# mowgli_1.net
KiCad netlist of a schematic drawn in EAGLE
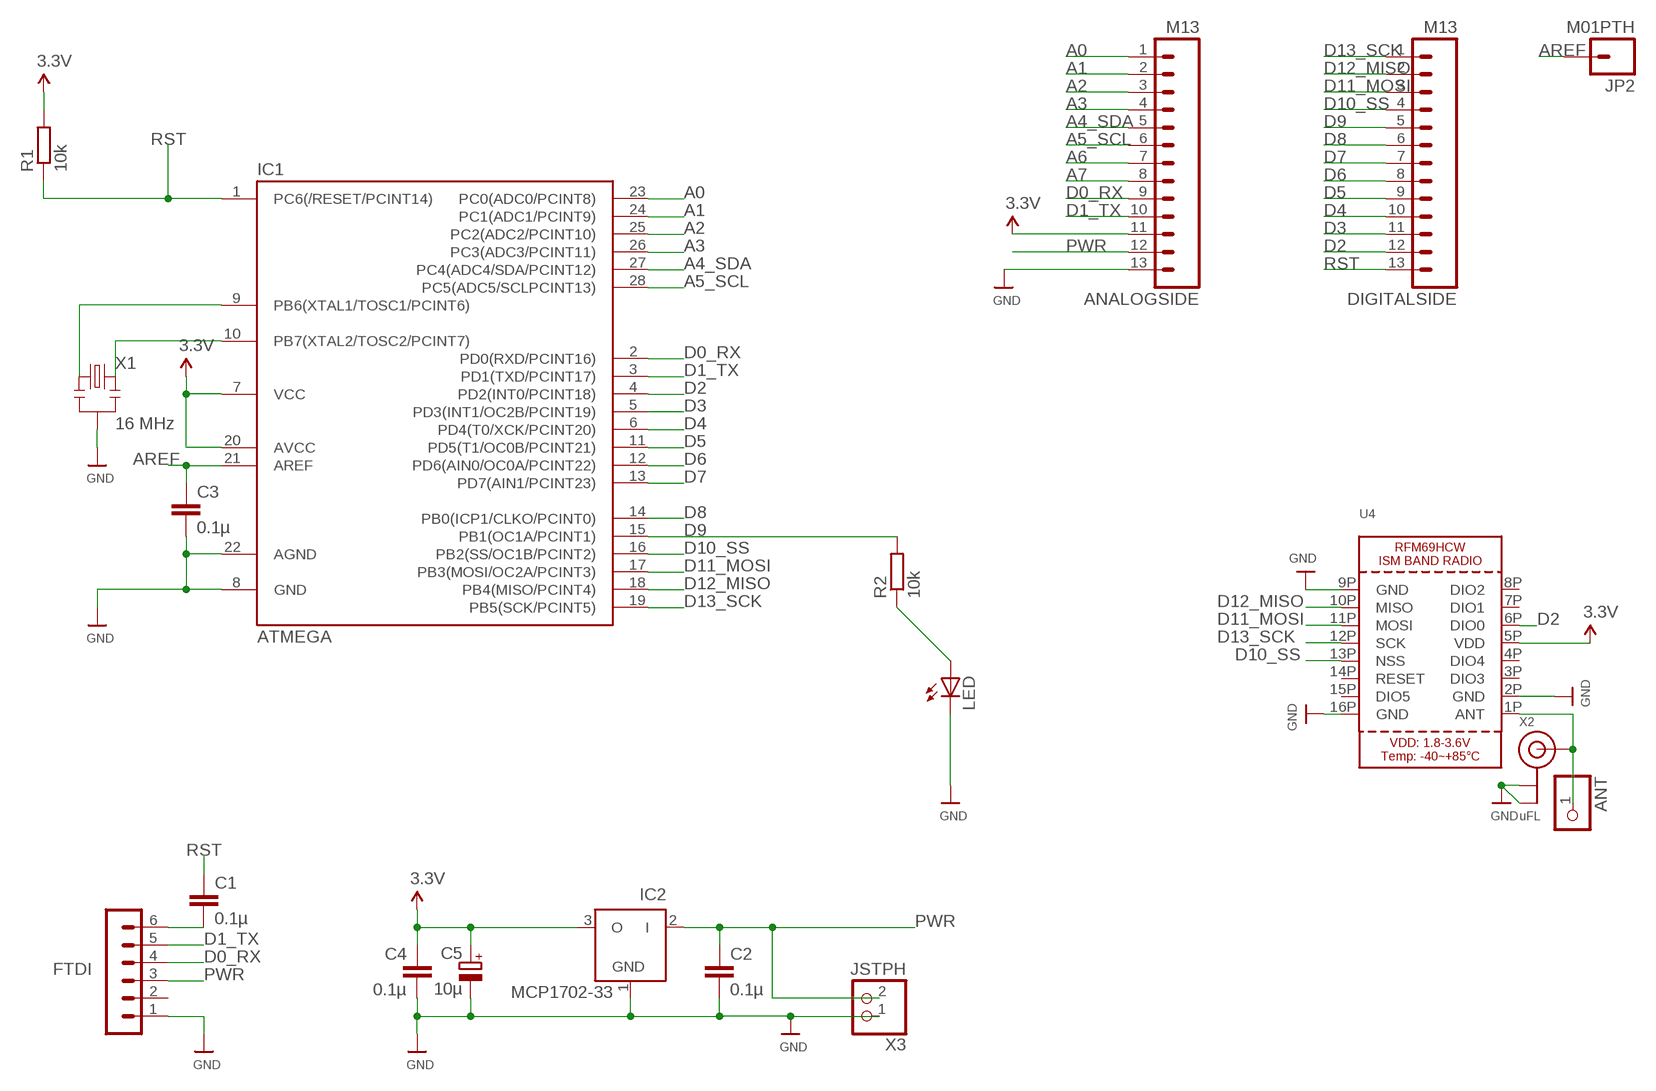
[diagram p0: schematic, sheet 1]

(export (version "E")
  (design (tool "Eeschema 10.0.6"))
  (components
    (comp (ref "ANALOGSIDE")
      (value "M13")
      (footprint "eagle-import:1X13")
      (libsource (lib "eagle-import") (part "M13"))
    )
    (comp (ref "ANT")
      (value "HEADER-1X1ROUND")
      (footprint "eagle-import:1X01_ROUND")
      (libsource (lib "eagle-import") (part "HEADER-1X1ROUND"))
    )
    (comp (ref "C1")
      (value "0.1µ")
      (footprint "eagle-import:C025-024X044")
      (libsource (lib "eagle-import") (part "C-EU025-024X044"))
    )
    (comp (ref "C2")
      (value "0.1µ")
      (footprint "eagle-import:C025-024X044")
      (libsource (lib "eagle-import") (part "C-EU025-024X044"))
    )
    (comp (ref "C3")
      (value "0.1µ")
      (footprint "eagle-import:C025-024X044")
      (libsource (lib "eagle-import") (part "C-EU025-024X044"))
    )
    (comp (ref "C4")
      (value "0.1µ")
      (footprint "eagle-import:C025-024X044")
      (libsource (lib "eagle-import") (part "C-EU025-024X044"))
    )
    (comp (ref "C5")
      (value "10µ")
      (footprint "eagle-import:E1,8-4")
      (libsource (lib "eagle-import") (part "CPOL-EUE1.8-4"))
    )
    (comp (ref "DIGITALSIDE")
      (value "M13")
      (footprint "eagle-import:1X13")
      (libsource (lib "eagle-import") (part "M13"))
    )
    (comp (ref "FTDI")
      (value "FTDI")
      (footprint "eagle-import:MA06-1")
      (libsource (lib "eagle-import") (part "MA06-1"))
    )
    (comp (ref "IC1")
      (value "ATMEGA")
      (footprint "eagle-import:DIL28-3")
      (libsource (lib "eagle-import") (part "ATMEGA48/88/168-PU"))
    )
    (comp (ref "IC2")
      (value "MCP1702-33")
      (footprint "eagle-import:TO92")
      (libsource (lib "eagle-import") (part "MCP1702Z"))
    )
    (comp (ref "JP2")
      (value "M01PTH")
      (footprint "eagle-import:1X01")
      (libsource (lib "eagle-import") (part "M01PTH"))
    )
    (comp (ref "LED")
      (value "LED3MM")
      (footprint "eagle-import:LED3MM")
      (libsource (lib "eagle-import") (part "LED3MM"))
    )
    (comp (ref "R1")
      (value "10k")
      (footprint "eagle-import:0204_7")
      (libsource (lib "eagle-import") (part "R-EU_0204/7"))
    )
    (comp (ref "R2")
      (value "10k")
      (footprint "eagle-import:0204_7")
      (libsource (lib "eagle-import") (part "R-EU_0204/7"))
    )
    (comp (ref "U4")
      (value "RFM69HCW_SMT")
      (footprint "eagle-import:RFMHCW_SMT")
      (libsource (lib "eagle-import") (part "RFM69HCW_SMT"))
    )
    (comp (ref "X1")
      (value "16 MHz")
      (footprint "eagle-import:RESONATOR-PTH")
      (libsource (lib "eagle-import") (part "RESONATORPTH"))
    )
    (comp (ref "X2")
      (value "uFL")
      (footprint "eagle-import:U.FL")
      (libsource (lib "eagle-import") (part "ANTENNA_U.FL"))
    )
    (comp (ref "X3")
      (value "JSTPH")
      (footprint "eagle-import:JSTPH2")
      (libsource (lib "eagle-import") (part "CON_JST_PH_2PIN"))
    )
  )
  (nets
    (net (code "1") (name "/A0") (class "Default")
      (node (ref "ANALOGSIDE") (pin "1") (pinfunction "1_1") (pintype "passive"))
      (node (ref "IC1") (pin "23") (pinfunction "PC0(ADC0/PCINT8)_23") (pintype "bidirectional"))
    )
    (net (code "2") (name "/A1") (class "Default")
      (node (ref "ANALOGSIDE") (pin "2") (pinfunction "2_2") (pintype "passive"))
      (node (ref "IC1") (pin "24") (pinfunction "PC1(ADC1/PCINT9)_24") (pintype "bidirectional"))
    )
    (net (code "3") (name "/A2") (class "Default")
      (node (ref "ANALOGSIDE") (pin "3") (pinfunction "3_3") (pintype "passive"))
      (node (ref "IC1") (pin "25") (pinfunction "PC2(ADC2/PCINT10)_25") (pintype "bidirectional"))
    )
    (net (code "4") (name "/A3") (class "Default")
      (node (ref "ANALOGSIDE") (pin "4") (pinfunction "4_4") (pintype "passive"))
      (node (ref "IC1") (pin "26") (pinfunction "PC3(ADC3/PCINT11)_26") (pintype "bidirectional"))
    )
    (net (code "5") (name "/A4_SDA") (class "Default")
      (node (ref "ANALOGSIDE") (pin "5") (pinfunction "5_5") (pintype "passive"))
      (node (ref "IC1") (pin "27") (pinfunction "PC4(ADC4/SDA/PCINT12)_27") (pintype "bidirectional"))
    )
    (net (code "6") (name "/A5_SCL") (class "Default")
      (node (ref "ANALOGSIDE") (pin "6") (pinfunction "6_6") (pintype "passive"))
      (node (ref "IC1") (pin "28") (pinfunction "PC5(ADC5/SCLPCINT13)_28") (pintype "bidirectional"))
    )
    (net (code "7") (name "/A6") (class "Default")
      (node (ref "ANALOGSIDE") (pin "7") (pinfunction "7_7") (pintype "passive"))
    )
    (net (code "8") (name "/A7") (class "Default")
      (node (ref "ANALOGSIDE") (pin "8") (pinfunction "8_8") (pintype "passive"))
    )
    (net (code "9") (name "/AREF") (class "Default")
      (node (ref "C3") (pin "1") (pinfunction "1_1") (pintype "passive"))
      (node (ref "IC1") (pin "21") (pinfunction "AREF_21") (pintype "passive"))
      (node (ref "JP2") (pin "1") (pinfunction "1_1") (pintype "passive"))
    )
    (net (code "10") (name "/D0_RX") (class "Default")
      (node (ref "ANALOGSIDE") (pin "9") (pinfunction "9_9") (pintype "passive"))
      (node (ref "FTDI") (pin "4") (pinfunction "4_4") (pintype "passive"))
      (node (ref "IC1") (pin "2") (pinfunction "PD0(RXD/PCINT16)_2") (pintype "bidirectional"))
    )
    (net (code "11") (name "/D1_TX") (class "Default")
      (node (ref "ANALOGSIDE") (pin "10") (pinfunction "10_10") (pintype "passive"))
      (node (ref "FTDI") (pin "5") (pinfunction "5_5") (pintype "passive"))
      (node (ref "IC1") (pin "3") (pinfunction "PD1(TXD/PCINT17)_3") (pintype "bidirectional"))
    )
    (net (code "12") (name "/D2") (class "Default")
      (node (ref "DIGITALSIDE") (pin "12") (pinfunction "12_12") (pintype "passive"))
      (node (ref "IC1") (pin "4") (pinfunction "PD2(INT0/PCINT18)_4") (pintype "bidirectional"))
      (node (ref "U4") (pin "6P") (pinfunction "DIO0_6P") (pintype "bidirectional"))
    )
    (net (code "13") (name "/D3") (class "Default")
      (node (ref "DIGITALSIDE") (pin "11") (pinfunction "11_11") (pintype "passive"))
      (node (ref "IC1") (pin "5") (pinfunction "PD3(INT1/OC2B/PCINT19)_5") (pintype "bidirectional"))
    )
    (net (code "14") (name "/D4") (class "Default")
      (node (ref "DIGITALSIDE") (pin "10") (pinfunction "10_10") (pintype "passive"))
      (node (ref "IC1") (pin "6") (pinfunction "PD4(T0/XCK/PCINT20)_6") (pintype "bidirectional"))
    )
    (net (code "15") (name "/D5") (class "Default")
      (node (ref "DIGITALSIDE") (pin "9") (pinfunction "9_9") (pintype "passive"))
      (node (ref "IC1") (pin "11") (pinfunction "PD5(T1/OC0B/PCINT21)_11") (pintype "bidirectional"))
    )
    (net (code "16") (name "/D6") (class "Default")
      (node (ref "DIGITALSIDE") (pin "8") (pinfunction "8_8") (pintype "passive"))
      (node (ref "IC1") (pin "12") (pinfunction "PD6(AIN0/OC0A/PCINT22)_12") (pintype "bidirectional"))
    )
    (net (code "17") (name "/D7") (class "Default")
      (node (ref "DIGITALSIDE") (pin "7") (pinfunction "7_7") (pintype "passive"))
      (node (ref "IC1") (pin "13") (pinfunction "PD7(AIN1/PCINT23)_13") (pintype "bidirectional"))
    )
    (net (code "18") (name "/D8") (class "Default")
      (node (ref "DIGITALSIDE") (pin "6") (pinfunction "6_6") (pintype "passive"))
      (node (ref "IC1") (pin "14") (pinfunction "PB0(ICP1/CLKO/PCINT0)_14") (pintype "bidirectional"))
    )
    (net (code "19") (name "/D9") (class "Default")
      (node (ref "DIGITALSIDE") (pin "5") (pinfunction "5_5") (pintype "passive"))
      (node (ref "IC1") (pin "15") (pinfunction "PB1(OC1A/PCINT1)_15") (pintype "bidirectional"))
      (node (ref "R2") (pin "2") (pinfunction "2_2") (pintype "passive"))
    )
    (net (code "20") (name "/D10_SS") (class "Default")
      (node (ref "DIGITALSIDE") (pin "4") (pinfunction "4_4") (pintype "passive"))
      (node (ref "IC1") (pin "16") (pinfunction "PB2(SS/OC1B/PCINT2)_16") (pintype "bidirectional"))
      (node (ref "U4") (pin "13P") (pinfunction "NSS_13P") (pintype "input"))
    )
    (net (code "21") (name "/D11_MOSI") (class "Default")
      (node (ref "DIGITALSIDE") (pin "3") (pinfunction "3_3") (pintype "passive"))
      (node (ref "IC1") (pin "17") (pinfunction "PB3(MOSI/OC2A/PCINT3)_17") (pintype "bidirectional"))
      (node (ref "U4") (pin "11P") (pinfunction "MOSI_11P") (pintype "input"))
    )
    (net (code "22") (name "/D12_MISO") (class "Default")
      (node (ref "DIGITALSIDE") (pin "2") (pinfunction "2_2") (pintype "passive"))
      (node (ref "IC1") (pin "18") (pinfunction "PB4(MISO/PCINT4)_18") (pintype "bidirectional"))
      (node (ref "U4") (pin "10P") (pinfunction "MISO_10P") (pintype "output"))
    )
    (net (code "23") (name "/D13_SCK") (class "Default")
      (node (ref "DIGITALSIDE") (pin "1") (pinfunction "1_1") (pintype "passive"))
      (node (ref "IC1") (pin "19") (pinfunction "PB5(SCK/PCINT5)_19") (pintype "bidirectional"))
      (node (ref "U4") (pin "12P") (pinfunction "SCK_12P") (pintype "input"))
    )
    (net (code "24") (name "/PWR") (class "Default")
      (node (ref "ANALOGSIDE") (pin "12") (pinfunction "12_12") (pintype "passive"))
      (node (ref "C2") (pin "1") (pinfunction "1_1") (pintype "passive"))
      (node (ref "FTDI") (pin "3") (pinfunction "3_3") (pintype "passive"))
      (node (ref "IC2") (pin "2") (pinfunction "I_2") (pintype "input"))
      (node (ref "X3") (pin "2") (pinfunction "2_2") (pintype "passive"))
    )
    (net (code "25") (name "/RST") (class "Default")
      (node (ref "C1") (pin "1") (pinfunction "1_1") (pintype "passive"))
      (node (ref "DIGITALSIDE") (pin "13") (pinfunction "13_13") (pintype "passive"))
      (node (ref "IC1") (pin "1") (pinfunction "PC6(/RESET/PCINT14)_1") (pintype "bidirectional"))
      (node (ref "R1") (pin "1") (pinfunction "1_1") (pintype "passive"))
    )
    (net (code "26") (name "3.3V") (class "Default")
      (node (ref "ANALOGSIDE") (pin "11") (pinfunction "11_11") (pintype "passive"))
      (node (ref "C4") (pin "1") (pinfunction "1_1") (pintype "passive"))
      (node (ref "C5") (pin "+") (pinfunction "+_+") (pintype "passive"))
      (node (ref "IC1") (pin "20") (pinfunction "AVCC_20") (pintype "passive"))
      (node (ref "IC1") (pin "7") (pinfunction "VCC_7") (pintype "power_in"))
      (node (ref "IC2") (pin "3") (pinfunction "O_3") (pintype "input"))
      (node (ref "R1") (pin "2") (pinfunction "2_2") (pintype "passive"))
      (node (ref "U4") (pin "5P") (pinfunction "VDD_5P") (pintype "power_in"))
    )
    (net (code "27") (name "GND") (class "Default")
      (node (ref "ANALOGSIDE") (pin "13") (pinfunction "13_13") (pintype "passive"))
      (node (ref "C2") (pin "2") (pinfunction "2_2") (pintype "passive"))
      (node (ref "C3") (pin "2") (pinfunction "2_2") (pintype "passive"))
      (node (ref "C4") (pin "2") (pinfunction "2_2") (pintype "passive"))
      (node (ref "C5") (pin "-") (pinfunction "-_-") (pintype "passive"))
      (node (ref "FTDI") (pin "1") (pinfunction "1_1") (pintype "passive"))
      (node (ref "IC1") (pin "22") (pinfunction "AGND_22") (pintype "power_in"))
      (node (ref "IC1") (pin "8") (pinfunction "GND_8") (pintype "power_in"))
      (node (ref "IC2") (pin "1") (pinfunction "GND_1") (pintype "power_in"))
      (node (ref "LED") (pin "K") (pinfunction "C_K") (pintype "passive"))
      (node (ref "U4") (pin "16P") (pinfunction "GND_16P") (pintype "power_in"))
      (node (ref "U4") (pin "2P") (pinfunction "GND_2P") (pintype "power_in"))
      (node (ref "U4") (pin "9P") (pinfunction "GND_9P") (pintype "power_in"))
      (node (ref "X1") (pin "2") (pinfunction "2_2") (pintype "passive"))
      (node (ref "X2") (pin "1") (pinfunction "GND_1") (pintype "passive"))
      (node (ref "X2") (pin "2") (pinfunction "GND_2") (pintype "passive"))
      (node (ref "X3") (pin "1") (pinfunction "1_1") (pintype "passive"))
    )
    (net (code "28") (name "Net-(C1-Pad2)") (class "Default")
      (node (ref "C1") (pin "2") (pinfunction "2_2") (pintype "passive"))
      (node (ref "FTDI") (pin "6") (pinfunction "6_6") (pintype "passive"))
    )
    (net (code "29") (name "Net-(IC1-PB6(XTAL1{slash}TOSC1{slash}PCINT6))") (class "Default")
      (node (ref "IC1") (pin "9") (pinfunction "PB6(XTAL1/TOSC1/PCINT6)_9") (pintype "bidirectional"))
      (node (ref "X1") (pin "1") (pinfunction "1_1") (pintype "passive"))
    )
    (net (code "30") (name "Net-(IC1-PB7(XTAL2{slash}TOSC2{slash}PCINT7))") (class "Default")
      (node (ref "IC1") (pin "10") (pinfunction "PB7(XTAL2/TOSC2/PCINT7)_10") (pintype "bidirectional"))
      (node (ref "X1") (pin "3") (pinfunction "3_3") (pintype "passive"))
    )
    (net (code "31") (name "Net-(LED-PadA)") (class "Default")
      (node (ref "LED") (pin "A") (pinfunction "A_A") (pintype "passive"))
      (node (ref "R2") (pin "1") (pinfunction "1_1") (pintype "passive"))
    )
    (net (code "32") (name "Net-(U4-ANT)") (class "Default")
      (node (ref "ANT") (pin "1") (pinfunction "1_1") (pintype "passive"))
      (node (ref "U4") (pin "1P") (pinfunction "ANT_1P") (pintype "bidirectional"))
      (node (ref "X2") (pin "3") (pinfunction "SIGNAL_3") (pintype "passive"))
    )
    (net (code "33") (name "unconnected-(FTDI-Pad2)") (class "Default")
      (node (ref "FTDI") (pin "2") (pinfunction "2_2") (pintype "passive"))
    )
    (net (code "34") (name "unconnected-(U4-DIO1-Pad7P)") (class "Default")
      (node (ref "U4") (pin "7P") (pinfunction "DIO1_7P") (pintype "bidirectional"))
    )
    (net (code "35") (name "unconnected-(U4-DIO2-Pad8P)") (class "Default")
      (node (ref "U4") (pin "8P") (pinfunction "DIO2_8P") (pintype "bidirectional"))
    )
    (net (code "36") (name "unconnected-(U4-DIO3-Pad3P)") (class "Default")
      (node (ref "U4") (pin "3P") (pinfunction "DIO3_3P") (pintype "bidirectional"))
    )
    (net (code "37") (name "unconnected-(U4-DIO4-Pad4P)") (class "Default")
      (node (ref "U4") (pin "4P") (pinfunction "DIO4_4P") (pintype "bidirectional"))
    )
    (net (code "38") (name "unconnected-(U4-DIO5-Pad15P)") (class "Default")
      (node (ref "U4") (pin "15P") (pinfunction "DIO5_15P") (pintype "bidirectional"))
    )
    (net (code "39") (name "unconnected-(U4-RESET-Pad14P)") (class "Default")
      (node (ref "U4") (pin "14P") (pinfunction "RESET_14P") (pintype "input"))
    )
  )
)
